# Board_0.net
KiCad netlist of a schematic drawn in EAGLE
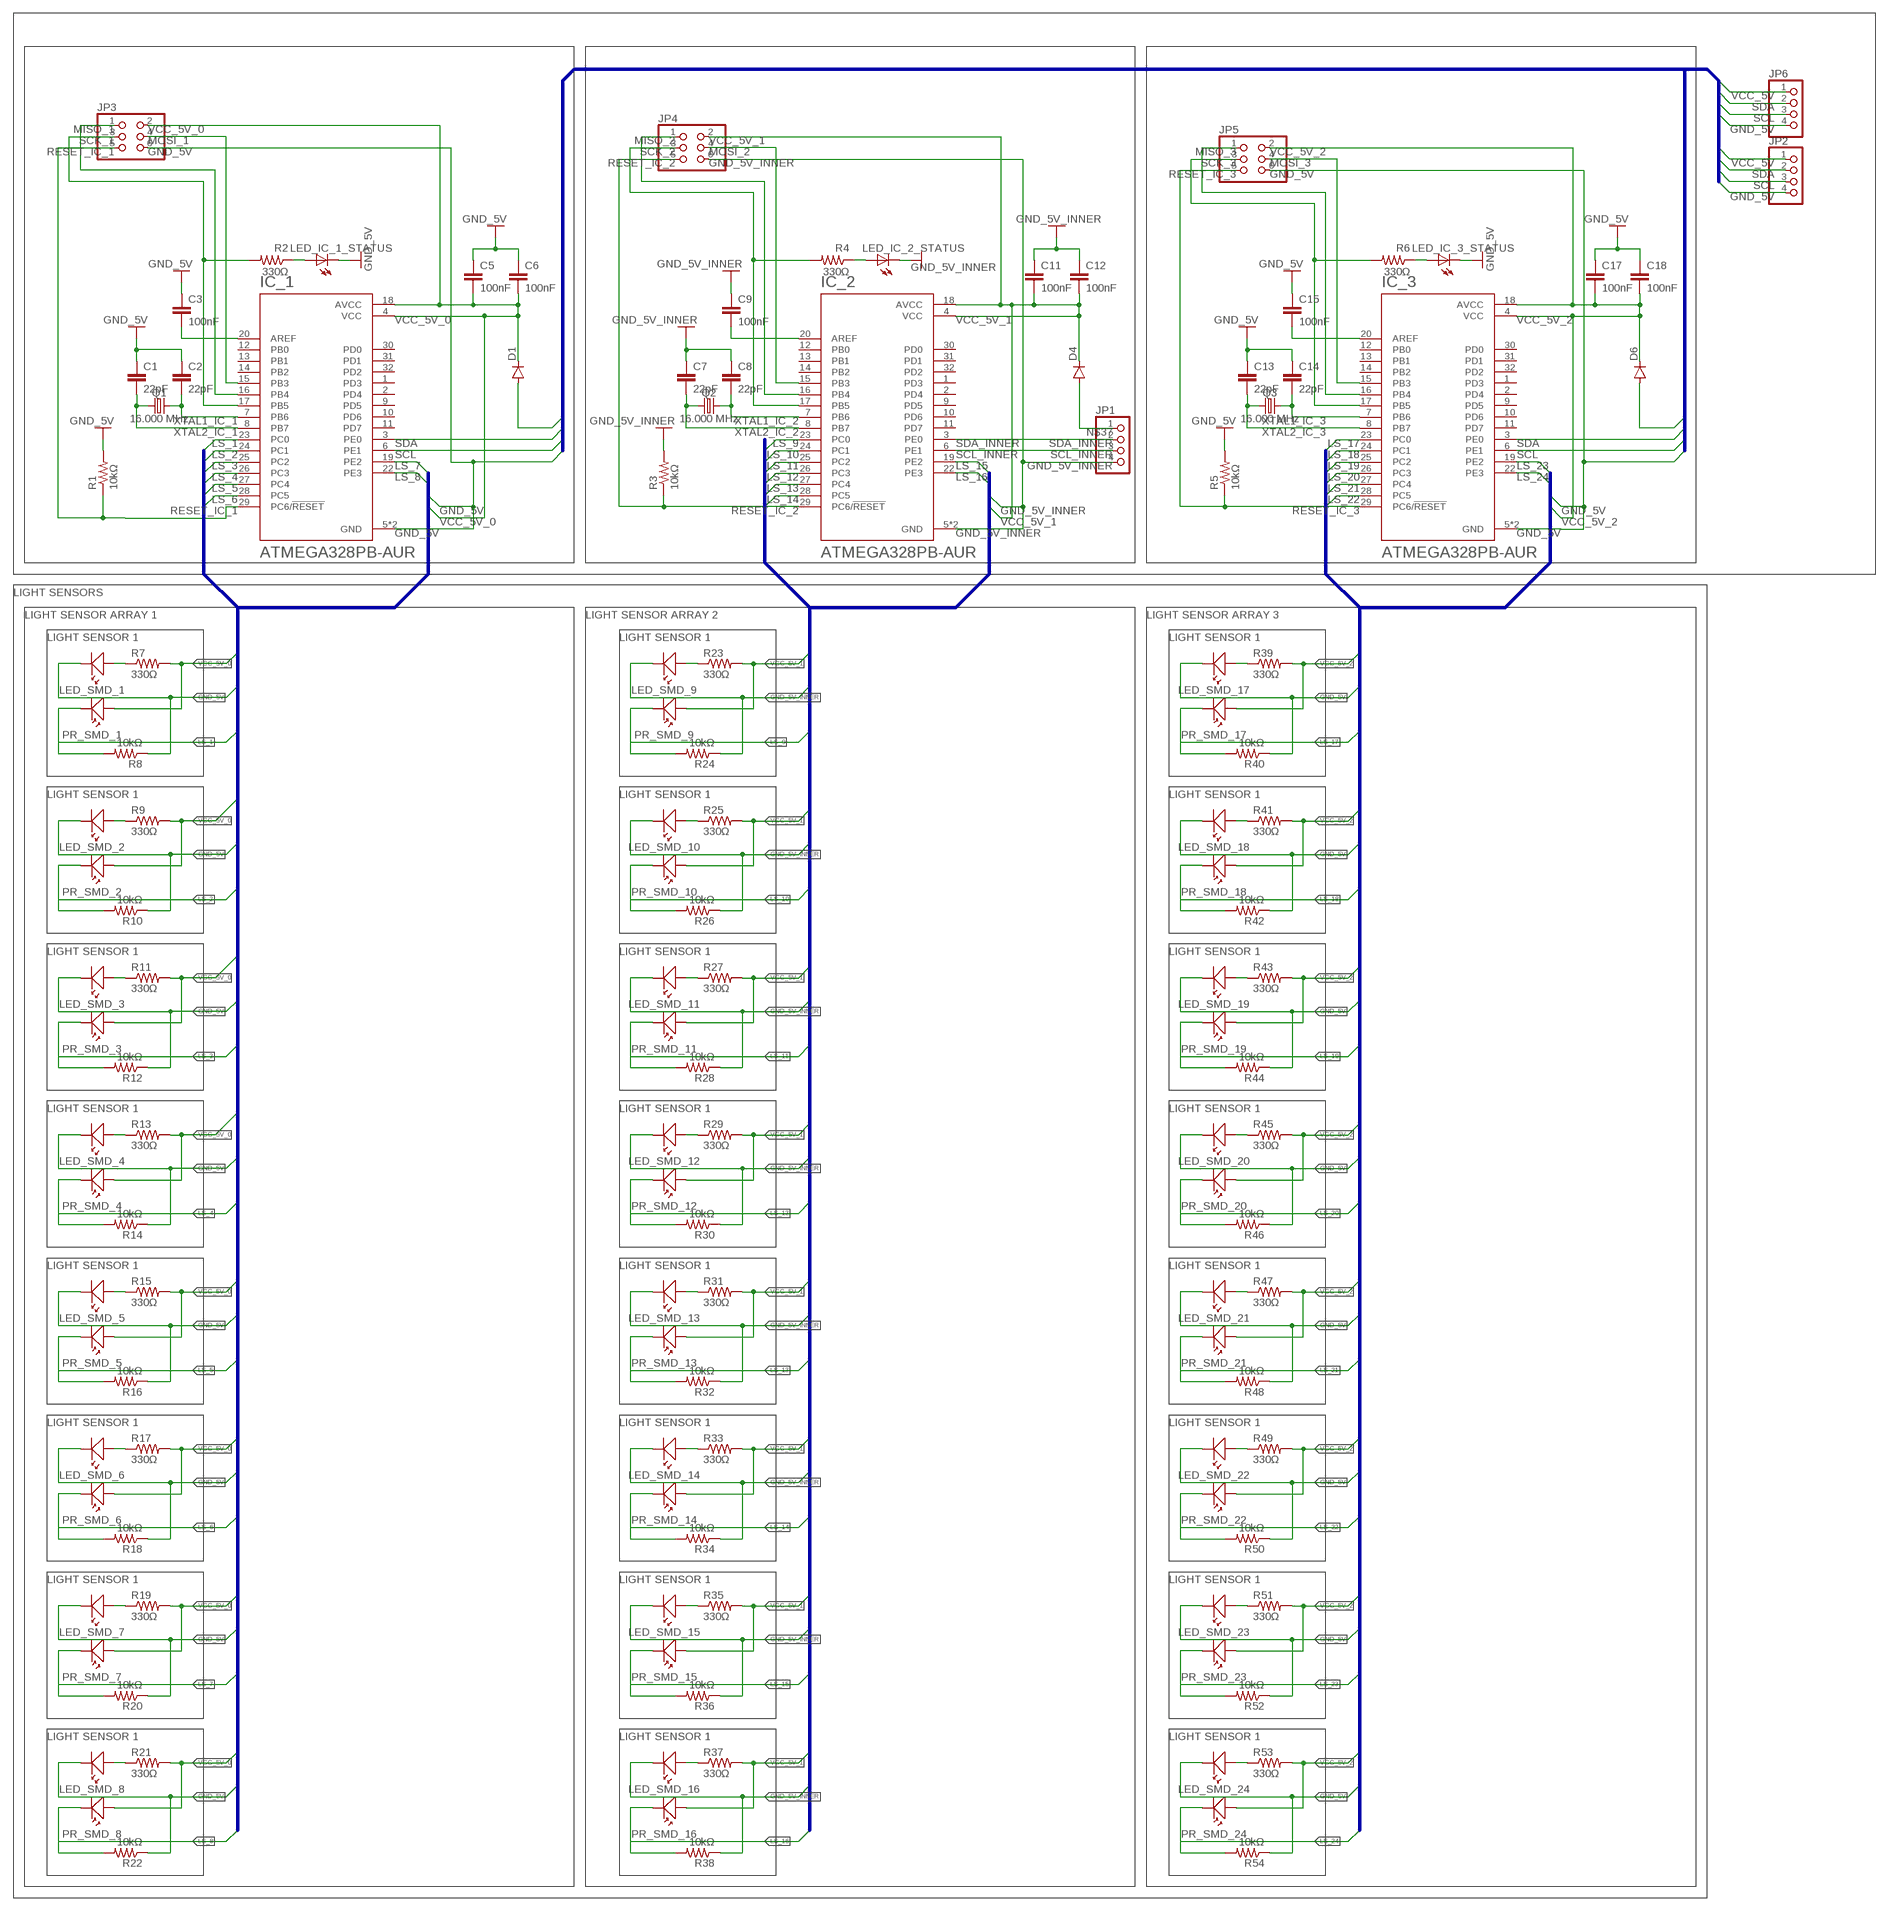
[diagram p0: schematic, sheet 1]

(export (version "E")
  (design (tool "Eeschema 10.0.6"))
  (components
    (comp (ref "C1")
      (value "22pF")
      (footprint "eagle-import:C1206")
      (libsource (lib "eagle-import") (part "C-EUC1206"))
    )
    (comp (ref "C2")
      (value "22pF")
      (footprint "eagle-import:C1206")
      (libsource (lib "eagle-import") (part "C-EUC1206"))
    )
    (comp (ref "C3")
      (value "100nF")
      (footprint "eagle-import:C1206")
      (libsource (lib "eagle-import") (part "C-EUC1206"))
    )
    (comp (ref "C5")
      (value "100nF")
      (footprint "eagle-import:C1206")
      (libsource (lib "eagle-import") (part "C-EUC1206"))
    )
    (comp (ref "C6")
      (value "100nF")
      (footprint "eagle-import:C1206")
      (libsource (lib "eagle-import") (part "C-EUC1206"))
    )
    (comp (ref "C7")
      (value "22pF")
      (footprint "eagle-import:C1206")
      (libsource (lib "eagle-import") (part "C-EUC1206"))
    )
    (comp (ref "C8")
      (value "22pF")
      (footprint "eagle-import:C1206")
      (libsource (lib "eagle-import") (part "C-EUC1206"))
    )
    (comp (ref "C9")
      (value "100nF")
      (footprint "eagle-import:C1206")
      (libsource (lib "eagle-import") (part "C-EUC1206"))
    )
    (comp (ref "C11")
      (value "100nF")
      (footprint "eagle-import:C1206")
      (libsource (lib "eagle-import") (part "C-EUC1206"))
    )
    (comp (ref "C12")
      (value "100nF")
      (footprint "eagle-import:C1206")
      (libsource (lib "eagle-import") (part "C-EUC1206"))
    )
    (comp (ref "C13")
      (value "22pF")
      (footprint "eagle-import:C1206")
      (libsource (lib "eagle-import") (part "C-EUC1206"))
    )
    (comp (ref "C14")
      (value "22pF")
      (footprint "eagle-import:C1206")
      (libsource (lib "eagle-import") (part "C-EUC1206"))
    )
    (comp (ref "C15")
      (value "100nF")
      (footprint "eagle-import:C1206")
      (libsource (lib "eagle-import") (part "C-EUC1206"))
    )
    (comp (ref "C17")
      (value "100nF")
      (footprint "eagle-import:C1206")
      (libsource (lib "eagle-import") (part "C-EUC1206"))
    )
    (comp (ref "C18")
      (value "100nF")
      (footprint "eagle-import:C1206")
      (libsource (lib "eagle-import") (part "C-EUC1206"))
    )
    (comp (ref "D1")
      (value "DIODE-SOD123")
      (footprint "eagle-import:SOD123")
      (libsource (lib "eagle-import") (part "DIODE-SOD123"))
    )
    (comp (ref "D4")
      (value "DIODE-SOD123")
      (footprint "eagle-import:SOD123")
      (libsource (lib "eagle-import") (part "DIODE-SOD123"))
    )
    (comp (ref "D6")
      (value "DIODE-SOD123")
      (footprint "eagle-import:SOD123")
      (libsource (lib "eagle-import") (part "DIODE-SOD123"))
    )
    (comp (ref "IC_1")
      (value "ATMEGA328PB-AUR")
      (footprint "eagle-import:QFP80P900X900X120-32N")
      (fields (field (name "MF") "Microchip"))
      (libsource (lib "eagle-import") (part "ATMEGA328PB-AUR"))
    )
    (comp (ref "IC_2")
      (value "ATMEGA328PB-AUR")
      (footprint "eagle-import:QFP80P900X900X120-32N")
      (fields (field (name "MF") "Microchip"))
      (libsource (lib "eagle-import") (part "ATMEGA328PB-AUR"))
    )
    (comp (ref "IC_3")
      (value "ATMEGA328PB-AUR")
      (footprint "eagle-import:QFP80P900X900X120-32N")
      (fields (field (name "MF") "Microchip"))
      (libsource (lib "eagle-import") (part "ATMEGA328PB-AUR"))
    )
    (comp (ref "JP1")
      (value "PINHD-1X4_2.54-SMD")
      (footprint "eagle-import:1X04SMD")
      (libsource (lib "eagle-import") (part "PINHD-1X4_2.54-SMD"))
    )
    (comp (ref "JP2")
      (value "PINHD-1X4_2.54-SMD")
      (footprint "eagle-import:1X04SMD")
      (libsource (lib "eagle-import") (part "PINHD-1X4_2.54-SMD"))
    )
    (comp (ref "JP3")
      (value "PINHD-2X3_2.54-SMD")
      (footprint "eagle-import:2X03SMD")
      (libsource (lib "eagle-import") (part "PINHD-2X3_2.54-SMD"))
    )
    (comp (ref "JP4")
      (value "PINHD-2X3_2.54-SMD")
      (footprint "eagle-import:2X03SMD")
      (libsource (lib "eagle-import") (part "PINHD-2X3_2.54-SMD"))
    )
    (comp (ref "JP5")
      (value "PINHD-2X3_2.54-SMD")
      (footprint "eagle-import:2X03SMD")
      (libsource (lib "eagle-import") (part "PINHD-2X3_2.54-SMD"))
    )
    (comp (ref "JP6")
      (value "PINHD-1X4_2.54-SMD")
      (footprint "eagle-import:1X04SMD")
      (libsource (lib "eagle-import") (part "PINHD-1X4_2.54-SMD"))
    )
    (comp (ref "LED_IC_1_STATUS")
      (value "LEDP-LCC-2")
      (footprint "eagle-import:P-LCC-2")
      (libsource (lib "eagle-import") (part "LEDP-LCC-2"))
    )
    (comp (ref "LED_IC_2_STATUS")
      (value "LEDP-LCC-2")
      (footprint "eagle-import:P-LCC-2")
      (libsource (lib "eagle-import") (part "LEDP-LCC-2"))
    )
    (comp (ref "LED_IC_3_STATUS")
      (value "LEDP-LCC-2")
      (footprint "eagle-import:P-LCC-2")
      (libsource (lib "eagle-import") (part "LEDP-LCC-2"))
    )
    (comp (ref "LED_SMD_1")
      (value "SMD_LED_3MM")
      (footprint "eagle-import:SMD_LED_3MM")
      (libsource (lib "eagle-import") (part "SMD_LED_3MM"))
    )
    (comp (ref "LED_SMD_2")
      (value "SMD_LED_3MM")
      (footprint "eagle-import:SMD_LED_3MM")
      (libsource (lib "eagle-import") (part "SMD_LED_3MM"))
    )
    (comp (ref "LED_SMD_3")
      (value "SMD_LED_3MM")
      (footprint "eagle-import:SMD_LED_3MM")
      (libsource (lib "eagle-import") (part "SMD_LED_3MM"))
    )
    (comp (ref "LED_SMD_4")
      (value "SMD_LED_3MM")
      (footprint "eagle-import:SMD_LED_3MM")
      (libsource (lib "eagle-import") (part "SMD_LED_3MM"))
    )
    (comp (ref "LED_SMD_5")
      (value "SMD_LED_3MM")
      (footprint "eagle-import:SMD_LED_3MM")
      (libsource (lib "eagle-import") (part "SMD_LED_3MM"))
    )
    (comp (ref "LED_SMD_6")
      (value "SMD_LED_3MM")
      (footprint "eagle-import:SMD_LED_3MM")
      (libsource (lib "eagle-import") (part "SMD_LED_3MM"))
    )
    (comp (ref "LED_SMD_7")
      (value "SMD_LED_3MM")
      (footprint "eagle-import:SMD_LED_3MM")
      (libsource (lib "eagle-import") (part "SMD_LED_3MM"))
    )
    (comp (ref "LED_SMD_8")
      (value "SMD_LED_3MM")
      (footprint "eagle-import:SMD_LED_3MM")
      (libsource (lib "eagle-import") (part "SMD_LED_3MM"))
    )
    (comp (ref "LED_SMD_9")
      (value "SMD_LED_3MM")
      (footprint "eagle-import:SMD_LED_3MM")
      (libsource (lib "eagle-import") (part "SMD_LED_3MM"))
    )
    (comp (ref "LED_SMD_10")
      (value "SMD_LED_3MM")
      (footprint "eagle-import:SMD_LED_3MM")
      (libsource (lib "eagle-import") (part "SMD_LED_3MM"))
    )
    (comp (ref "LED_SMD_11")
      (value "SMD_LED_3MM")
      (footprint "eagle-import:SMD_LED_3MM")
      (libsource (lib "eagle-import") (part "SMD_LED_3MM"))
    )
    (comp (ref "LED_SMD_12")
      (value "SMD_LED_3MM")
      (footprint "eagle-import:SMD_LED_3MM")
      (libsource (lib "eagle-import") (part "SMD_LED_3MM"))
    )
    (comp (ref "LED_SMD_13")
      (value "SMD_LED_3MM")
      (footprint "eagle-import:SMD_LED_3MM")
      (libsource (lib "eagle-import") (part "SMD_LED_3MM"))
    )
    (comp (ref "LED_SMD_14")
      (value "SMD_LED_3MM")
      (footprint "eagle-import:SMD_LED_3MM")
      (libsource (lib "eagle-import") (part "SMD_LED_3MM"))
    )
    (comp (ref "LED_SMD_15")
      (value "SMD_LED_3MM")
      (footprint "eagle-import:SMD_LED_3MM")
      (libsource (lib "eagle-import") (part "SMD_LED_3MM"))
    )
    (comp (ref "LED_SMD_16")
      (value "SMD_LED_3MM")
      (footprint "eagle-import:SMD_LED_3MM")
      (libsource (lib "eagle-import") (part "SMD_LED_3MM"))
    )
    (comp (ref "LED_SMD_17")
      (value "SMD_LED_3MM")
      (footprint "eagle-import:SMD_LED_3MM")
      (libsource (lib "eagle-import") (part "SMD_LED_3MM"))
    )
    (comp (ref "LED_SMD_18")
      (value "SMD_LED_3MM")
      (footprint "eagle-import:SMD_LED_3MM")
      (libsource (lib "eagle-import") (part "SMD_LED_3MM"))
    )
    (comp (ref "LED_SMD_19")
      (value "SMD_LED_3MM")
      (footprint "eagle-import:SMD_LED_3MM")
      (libsource (lib "eagle-import") (part "SMD_LED_3MM"))
    )
    (comp (ref "LED_SMD_20")
      (value "SMD_LED_3MM")
      (footprint "eagle-import:SMD_LED_3MM")
      (libsource (lib "eagle-import") (part "SMD_LED_3MM"))
    )
    (comp (ref "LED_SMD_21")
      (value "SMD_LED_3MM")
      (footprint "eagle-import:SMD_LED_3MM")
      (libsource (lib "eagle-import") (part "SMD_LED_3MM"))
    )
    (comp (ref "LED_SMD_22")
      (value "SMD_LED_3MM")
      (footprint "eagle-import:SMD_LED_3MM")
      (libsource (lib "eagle-import") (part "SMD_LED_3MM"))
    )
    (comp (ref "LED_SMD_23")
      (value "SMD_LED_3MM")
      (footprint "eagle-import:SMD_LED_3MM")
      (libsource (lib "eagle-import") (part "SMD_LED_3MM"))
    )
    (comp (ref "LED_SMD_24")
      (value "SMD_LED_3MM")
      (footprint "eagle-import:SMD_LED_3MM")
      (libsource (lib "eagle-import") (part "SMD_LED_3MM"))
    )
    (comp (ref "PR_SMD_1")
      (value "SMD_PHOTORESISTOR_5MM")
      (footprint "eagle-import:SMD_PHOTORESISTOR_5MM")
      (libsource (lib "eagle-import") (part "SMD_PHOTORESISTOR_5MM"))
    )
    (comp (ref "PR_SMD_2")
      (value "SMD_PHOTORESISTOR_5MM")
      (footprint "eagle-import:SMD_PHOTORESISTOR_5MM")
      (libsource (lib "eagle-import") (part "SMD_PHOTORESISTOR_5MM"))
    )
    (comp (ref "PR_SMD_3")
      (value "SMD_PHOTORESISTOR_5MM")
      (footprint "eagle-import:SMD_PHOTORESISTOR_5MM")
      (libsource (lib "eagle-import") (part "SMD_PHOTORESISTOR_5MM"))
    )
    (comp (ref "PR_SMD_4")
      (value "SMD_PHOTORESISTOR_5MM")
      (footprint "eagle-import:SMD_PHOTORESISTOR_5MM")
      (libsource (lib "eagle-import") (part "SMD_PHOTORESISTOR_5MM"))
    )
    (comp (ref "PR_SMD_5")
      (value "SMD_PHOTORESISTOR_5MM")
      (footprint "eagle-import:SMD_PHOTORESISTOR_5MM")
      (libsource (lib "eagle-import") (part "SMD_PHOTORESISTOR_5MM"))
    )
    (comp (ref "PR_SMD_6")
      (value "SMD_PHOTORESISTOR_5MM")
      (footprint "eagle-import:SMD_PHOTORESISTOR_5MM")
      (libsource (lib "eagle-import") (part "SMD_PHOTORESISTOR_5MM"))
    )
    (comp (ref "PR_SMD_7")
      (value "SMD_PHOTORESISTOR_5MM")
      (footprint "eagle-import:SMD_PHOTORESISTOR_5MM")
      (libsource (lib "eagle-import") (part "SMD_PHOTORESISTOR_5MM"))
    )
    (comp (ref "PR_SMD_8")
      (value "SMD_PHOTORESISTOR_5MM")
      (footprint "eagle-import:SMD_PHOTORESISTOR_5MM")
      (libsource (lib "eagle-import") (part "SMD_PHOTORESISTOR_5MM"))
    )
    (comp (ref "PR_SMD_9")
      (value "SMD_PHOTORESISTOR_5MM")
      (footprint "eagle-import:SMD_PHOTORESISTOR_5MM")
      (libsource (lib "eagle-import") (part "SMD_PHOTORESISTOR_5MM"))
    )
    (comp (ref "PR_SMD_10")
      (value "SMD_PHOTORESISTOR_5MM")
      (footprint "eagle-import:SMD_PHOTORESISTOR_5MM")
      (libsource (lib "eagle-import") (part "SMD_PHOTORESISTOR_5MM"))
    )
    (comp (ref "PR_SMD_11")
      (value "SMD_PHOTORESISTOR_5MM")
      (footprint "eagle-import:SMD_PHOTORESISTOR_5MM")
      (libsource (lib "eagle-import") (part "SMD_PHOTORESISTOR_5MM"))
    )
    (comp (ref "PR_SMD_12")
      (value "SMD_PHOTORESISTOR_5MM")
      (footprint "eagle-import:SMD_PHOTORESISTOR_5MM")
      (libsource (lib "eagle-import") (part "SMD_PHOTORESISTOR_5MM"))
    )
    (comp (ref "PR_SMD_13")
      (value "SMD_PHOTORESISTOR_5MM")
      (footprint "eagle-import:SMD_PHOTORESISTOR_5MM")
      (libsource (lib "eagle-import") (part "SMD_PHOTORESISTOR_5MM"))
    )
    (comp (ref "PR_SMD_14")
      (value "SMD_PHOTORESISTOR_5MM")
      (footprint "eagle-import:SMD_PHOTORESISTOR_5MM")
      (libsource (lib "eagle-import") (part "SMD_PHOTORESISTOR_5MM"))
    )
    (comp (ref "PR_SMD_15")
      (value "SMD_PHOTORESISTOR_5MM")
      (footprint "eagle-import:SMD_PHOTORESISTOR_5MM")
      (libsource (lib "eagle-import") (part "SMD_PHOTORESISTOR_5MM"))
    )
    (comp (ref "PR_SMD_16")
      (value "SMD_PHOTORESISTOR_5MM")
      (footprint "eagle-import:SMD_PHOTORESISTOR_5MM")
      (libsource (lib "eagle-import") (part "SMD_PHOTORESISTOR_5MM"))
    )
    (comp (ref "PR_SMD_17")
      (value "SMD_PHOTORESISTOR_5MM")
      (footprint "eagle-import:SMD_PHOTORESISTOR_5MM")
      (libsource (lib "eagle-import") (part "SMD_PHOTORESISTOR_5MM"))
    )
    (comp (ref "PR_SMD_18")
      (value "SMD_PHOTORESISTOR_5MM")
      (footprint "eagle-import:SMD_PHOTORESISTOR_5MM")
      (libsource (lib "eagle-import") (part "SMD_PHOTORESISTOR_5MM"))
    )
    (comp (ref "PR_SMD_19")
      (value "SMD_PHOTORESISTOR_5MM")
      (footprint "eagle-import:SMD_PHOTORESISTOR_5MM")
      (libsource (lib "eagle-import") (part "SMD_PHOTORESISTOR_5MM"))
    )
    (comp (ref "PR_SMD_20")
      (value "SMD_PHOTORESISTOR_5MM")
      (footprint "eagle-import:SMD_PHOTORESISTOR_5MM")
      (libsource (lib "eagle-import") (part "SMD_PHOTORESISTOR_5MM"))
    )
    (comp (ref "PR_SMD_21")
      (value "SMD_PHOTORESISTOR_5MM")
      (footprint "eagle-import:SMD_PHOTORESISTOR_5MM")
      (libsource (lib "eagle-import") (part "SMD_PHOTORESISTOR_5MM"))
    )
    (comp (ref "PR_SMD_22")
      (value "SMD_PHOTORESISTOR_5MM")
      (footprint "eagle-import:SMD_PHOTORESISTOR_5MM")
      (libsource (lib "eagle-import") (part "SMD_PHOTORESISTOR_5MM"))
    )
    (comp (ref "PR_SMD_23")
      (value "SMD_PHOTORESISTOR_5MM")
      (footprint "eagle-import:SMD_PHOTORESISTOR_5MM")
      (libsource (lib "eagle-import") (part "SMD_PHOTORESISTOR_5MM"))
    )
    (comp (ref "PR_SMD_24")
      (value "SMD_PHOTORESISTOR_5MM")
      (footprint "eagle-import:SMD_PHOTORESISTOR_5MM")
      (libsource (lib "eagle-import") (part "SMD_PHOTORESISTOR_5MM"))
    )
    (comp (ref "Q1")
      (value "16.000 MHz")
      (footprint "eagle-import:CRYSTAL-SMD-5X3.2-4PAD")
      (libsource (lib "eagle-import") (part "CRYSTAL-16MHZSMD-5X3.2"))
    )
    (comp (ref "Q2")
      (value "16.000 MHz")
      (footprint "eagle-import:CRYSTAL-SMD-5X3.2-4PAD")
      (libsource (lib "eagle-import") (part "CRYSTAL-16MHZSMD-5X3.2"))
    )
    (comp (ref "Q3")
      (value "16.000 MHz")
      (footprint "eagle-import:CRYSTAL-SMD-5X3.2-4PAD")
      (libsource (lib "eagle-import") (part "CRYSTAL-16MHZSMD-5X3.2"))
    )
    (comp (ref "R1")
      (value "10kΩ")
      (footprint "eagle-import:R1206")
      (libsource (lib "eagle-import") (part "R-US_R1206"))
    )
    (comp (ref "R2")
      (value "330Ω")
      (footprint "eagle-import:R1206")
      (libsource (lib "eagle-import") (part "R-US_R1206"))
    )
    (comp (ref "R3")
      (value "10kΩ")
      (footprint "eagle-import:R1206")
      (libsource (lib "eagle-import") (part "R-US_R1206"))
    )
    (comp (ref "R4")
      (value "330Ω")
      (footprint "eagle-import:R1206")
      (libsource (lib "eagle-import") (part "R-US_R1206"))
    )
    (comp (ref "R5")
      (value "10kΩ")
      (footprint "eagle-import:R1206")
      (libsource (lib "eagle-import") (part "R-US_R1206"))
    )
    (comp (ref "R6")
      (value "330Ω")
      (footprint "eagle-import:R1206")
      (libsource (lib "eagle-import") (part "R-US_R1206"))
    )
    (comp (ref "R7")
      (value "330Ω")
      (footprint "eagle-import:R1206")
      (libsource (lib "eagle-import") (part "R-US_R1206"))
    )
    (comp (ref "R8")
      (value "10kΩ")
      (footprint "eagle-import:R1206")
      (libsource (lib "eagle-import") (part "R-US_R1206"))
    )
    (comp (ref "R9")
      (value "330Ω")
      (footprint "eagle-import:R1206")
      (libsource (lib "eagle-import") (part "R-US_R1206"))
    )
    (comp (ref "R10")
      (value "10kΩ")
      (footprint "eagle-import:R1206")
      (libsource (lib "eagle-import") (part "R-US_R1206"))
    )
    (comp (ref "R11")
      (value "330Ω")
      (footprint "eagle-import:R1206")
      (libsource (lib "eagle-import") (part "R-US_R1206"))
    )
    (comp (ref "R12")
      (value "10kΩ")
      (footprint "eagle-import:R1206")
      (libsource (lib "eagle-import") (part "R-US_R1206"))
    )
    (comp (ref "R13")
      (value "330Ω")
      (footprint "eagle-import:R1206")
      (libsource (lib "eagle-import") (part "R-US_R1206"))
    )
    (comp (ref "R14")
      (value "10kΩ")
      (footprint "eagle-import:R1206")
      (libsource (lib "eagle-import") (part "R-US_R1206"))
    )
    (comp (ref "R15")
      (value "330Ω")
      (footprint "eagle-import:R1206")
      (libsource (lib "eagle-import") (part "R-US_R1206"))
    )
    (comp (ref "R16")
      (value "10kΩ")
      (footprint "eagle-import:R1206")
      (libsource (lib "eagle-import") (part "R-US_R1206"))
    )
    (comp (ref "R17")
      (value "330Ω")
      (footprint "eagle-import:R1206")
      (libsource (lib "eagle-import") (part "R-US_R1206"))
    )
    (comp (ref "R18")
      (value "10kΩ")
      (footprint "eagle-import:R1206")
      (libsource (lib "eagle-import") (part "R-US_R1206"))
    )
    (comp (ref "R19")
      (value "330Ω")
      (footprint "eagle-import:R1206")
      (libsource (lib "eagle-import") (part "R-US_R1206"))
    )
    (comp (ref "R20")
      (value "10kΩ")
      (footprint "eagle-import:R1206")
      (libsource (lib "eagle-import") (part "R-US_R1206"))
    )
    (comp (ref "R21")
      (value "330Ω")
      (footprint "eagle-import:R1206")
      (libsource (lib "eagle-import") (part "R-US_R1206"))
    )
    (comp (ref "R22")
      (value "10kΩ")
      (footprint "eagle-import:R1206")
      (libsource (lib "eagle-import") (part "R-US_R1206"))
    )
    (comp (ref "R23")
      (value "330Ω")
      (footprint "eagle-import:R1206")
      (libsource (lib "eagle-import") (part "R-US_R1206"))
    )
    (comp (ref "R24")
      (value "10kΩ")
      (footprint "eagle-import:R1206")
      (libsource (lib "eagle-import") (part "R-US_R1206"))
    )
    (comp (ref "R25")
      (value "330Ω")
      (footprint "eagle-import:R1206")
      (libsource (lib "eagle-import") (part "R-US_R1206"))
    )
    (comp (ref "R26")
      (value "10kΩ")
      (footprint "eagle-import:R1206")
      (libsource (lib "eagle-import") (part "R-US_R1206"))
    )
    (comp (ref "R27")
      (value "330Ω")
      (footprint "eagle-import:R1206")
      (libsource (lib "eagle-import") (part "R-US_R1206"))
    )
    (comp (ref "R28")
      (value "10kΩ")
      (footprint "eagle-import:R1206")
      (libsource (lib "eagle-import") (part "R-US_R1206"))
    )
    (comp (ref "R29")
      (value "330Ω")
      (footprint "eagle-import:R1206")
      (libsource (lib "eagle-import") (part "R-US_R1206"))
    )
    (comp (ref "R30")
      (value "10kΩ")
      (footprint "eagle-import:R1206")
      (libsource (lib "eagle-import") (part "R-US_R1206"))
    )
    (comp (ref "R31")
      (value "330Ω")
      (footprint "eagle-import:R1206")
      (libsource (lib "eagle-import") (part "R-US_R1206"))
    )
    (comp (ref "R32")
      (value "10kΩ")
      (footprint "eagle-import:R1206")
      (libsource (lib "eagle-import") (part "R-US_R1206"))
    )
    (comp (ref "R33")
      (value "330Ω")
      (footprint "eagle-import:R1206")
      (libsource (lib "eagle-import") (part "R-US_R1206"))
    )
    (comp (ref "R34")
      (value "10kΩ")
      (footprint "eagle-import:R1206")
      (libsource (lib "eagle-import") (part "R-US_R1206"))
    )
    (comp (ref "R35")
      (value "330Ω")
      (footprint "eagle-import:R1206")
      (libsource (lib "eagle-import") (part "R-US_R1206"))
    )
    (comp (ref "R36")
      (value "10kΩ")
      (footprint "eagle-import:R1206")
      (libsource (lib "eagle-import") (part "R-US_R1206"))
    )
    (comp (ref "R37")
      (value "330Ω")
      (footprint "eagle-import:R1206")
      (libsource (lib "eagle-import") (part "R-US_R1206"))
    )
    (comp (ref "R38")
      (value "10kΩ")
      (footprint "eagle-import:R1206")
      (libsource (lib "eagle-import") (part "R-US_R1206"))
    )
    (comp (ref "R39")
      (value "330Ω")
      (footprint "eagle-import:R1206")
      (libsource (lib "eagle-import") (part "R-US_R1206"))
    )
    (comp (ref "R40")
      (value "10kΩ")
      (footprint "eagle-import:R1206")
      (libsource (lib "eagle-import") (part "R-US_R1206"))
    )
    (comp (ref "R41")
      (value "330Ω")
      (footprint "eagle-import:R1206")
      (libsource (lib "eagle-import") (part "R-US_R1206"))
    )
    (comp (ref "R42")
      (value "10kΩ")
      (footprint "eagle-import:R1206")
      (libsource (lib "eagle-import") (part "R-US_R1206"))
    )
    (comp (ref "R43")
      (value "330Ω")
      (footprint "eagle-import:R1206")
      (libsource (lib "eagle-import") (part "R-US_R1206"))
    )
    (comp (ref "R44")
      (value "10kΩ")
      (footprint "eagle-import:R1206")
      (libsource (lib "eagle-import") (part "R-US_R1206"))
    )
    (comp (ref "R45")
      (value "330Ω")
      (footprint "eagle-import:R1206")
      (libsource (lib "eagle-import") (part "R-US_R1206"))
    )
    (comp (ref "R46")
      (value "10kΩ")
      (footprint "eagle-import:R1206")
      (libsource (lib "eagle-import") (part "R-US_R1206"))
    )
    (comp (ref "R47")
      (value "330Ω")
      (footprint "eagle-import:R1206")
      (libsource (lib "eagle-import") (part "R-US_R1206"))
    )
    (comp (ref "R48")
      (value "10kΩ")
      (footprint "eagle-import:R1206")
      (libsource (lib "eagle-import") (part "R-US_R1206"))
    )
    (comp (ref "R49")
      (value "330Ω")
      (footprint "eagle-import:R1206")
      (libsource (lib "eagle-import") (part "R-US_R1206"))
    )
    (comp (ref "R50")
      (value "10kΩ")
      (footprint "eagle-import:R1206")
      (libsource (lib "eagle-import") (part "R-US_R1206"))
    )
    (comp (ref "R51")
      (value "330Ω")
      (footprint "eagle-import:R1206")
      (libsource (lib "eagle-import") (part "R-US_R1206"))
    )
    (comp (ref "R52")
      (value "10kΩ")
      (footprint "eagle-import:R1206")
      (libsource (lib "eagle-import") (part "R-US_R1206"))
    )
    (comp (ref "R53")
      (value "330Ω")
      (footprint "eagle-import:R1206")
      (libsource (lib "eagle-import") (part "R-US_R1206"))
    )
    (comp (ref "R54")
      (value "10kΩ")
      (footprint "eagle-import:R1206")
      (libsource (lib "eagle-import") (part "R-US_R1206"))
    )
  )
  (nets
    (net (code "1") (name "/MISO_1") (class "Default")
      (node (ref "IC_1") (pin "16") (pinfunction "PB4_16") (pintype "bidirectional"))
      (node (ref "JP3") (pin "1") (pinfunction "1_1") (pintype "passive"))
    )
    (net (code "2") (name "/MISO_2") (class "Default")
      (node (ref "IC_2") (pin "16") (pinfunction "PB4_16") (pintype "bidirectional"))
      (node (ref "JP4") (pin "1") (pinfunction "1_1") (pintype "passive"))
    )
    (net (code "3") (name "/MISO_3") (class "Default")
      (node (ref "IC_3") (pin "16") (pinfunction "PB4_16") (pintype "bidirectional"))
      (node (ref "JP5") (pin "1") (pinfunction "1_1") (pintype "passive"))
    )
    (net (code "4") (name "/MOSI_1") (class "Default")
      (node (ref "IC_1") (pin "15") (pinfunction "PB3_15") (pintype "bidirectional"))
      (node (ref "JP3") (pin "4") (pinfunction "4_4") (pintype "passive"))
    )
    (net (code "5") (name "/MOSI_2") (class "Default")
      (node (ref "IC_2") (pin "15") (pinfunction "PB3_15") (pintype "bidirectional"))
      (node (ref "JP4") (pin "4") (pinfunction "4_4") (pintype "passive"))
    )
    (net (code "6") (name "/MOSI_3") (class "Default")
      (node (ref "IC_3") (pin "15") (pinfunction "PB3_15") (pintype "bidirectional"))
      (node (ref "JP5") (pin "4") (pinfunction "4_4") (pintype "passive"))
    )
    (net (code "7") (name "/N$37") (class "Default")
      (node (ref "D4") (pin "A") (pinfunction "A_A") (pintype "passive"))
      (node (ref "JP1") (pin "1") (pinfunction "1_1") (pintype "passive"))
    )
    (net (code "8") (name "/RESET_IC_1") (class "Default")
      (node (ref "IC_1") (pin "29") (pinfunction "PC6/~{RESET}_29") (pintype "bidirectional"))
      (node (ref "JP3") (pin "5") (pinfunction "5_5") (pintype "passive"))
      (node (ref "R1") (pin "1") (pinfunction "1_1") (pintype "passive"))
    )
    (net (code "9") (name "/RESET_IC_2") (class "Default")
      (node (ref "IC_2") (pin "29") (pinfunction "PC6/~{RESET}_29") (pintype "bidirectional"))
      (node (ref "JP4") (pin "5") (pinfunction "5_5") (pintype "passive"))
      (node (ref "R3") (pin "1") (pinfunction "1_1") (pintype "passive"))
    )
    (net (code "10") (name "/RESET_IC_3") (class "Default")
      (node (ref "IC_3") (pin "29") (pinfunction "PC6/~{RESET}_29") (pintype "bidirectional"))
      (node (ref "JP5") (pin "5") (pinfunction "5_5") (pintype "passive"))
      (node (ref "R5") (pin "1") (pinfunction "1_1") (pintype "passive"))
    )
    (net (code "11") (name "/SCK_1") (class "Default")
      (node (ref "IC_1") (pin "17") (pinfunction "PB5_17") (pintype "bidirectional"))
      (node (ref "JP3") (pin "3") (pinfunction "3_3") (pintype "passive"))
      (node (ref "R2") (pin "2") (pinfunction "2_2") (pintype "passive"))
    )
    (net (code "12") (name "/SCK_2") (class "Default")
      (node (ref "IC_2") (pin "17") (pinfunction "PB5_17") (pintype "bidirectional"))
      (node (ref "JP4") (pin "3") (pinfunction "3_3") (pintype "passive"))
      (node (ref "R4") (pin "2") (pinfunction "2_2") (pintype "passive"))
    )
    (net (code "13") (name "/SCK_3") (class "Default")
      (node (ref "IC_3") (pin "17") (pinfunction "PB5_17") (pintype "bidirectional"))
      (node (ref "JP5") (pin "3") (pinfunction "3_3") (pintype "passive"))
      (node (ref "R6") (pin "2") (pinfunction "2_2") (pintype "passive"))
    )
    (net (code "14") (name "/SCL") (class "Default")
      (node (ref "IC_1") (pin "6") (pinfunction "PE1_6") (pintype "bidirectional"))
      (node (ref "IC_3") (pin "6") (pinfunction "PE1_6") (pintype "bidirectional"))
      (node (ref "JP2") (pin "3") (pinfunction "3_3") (pintype "passive"))
      (node (ref "JP6") (pin "3") (pinfunction "3_3") (pintype "passive"))
    )
    (net (code "15") (name "/SCL_INNER") (class "Default")
      (node (ref "IC_2") (pin "6") (pinfunction "PE1_6") (pintype "bidirectional"))
      (node (ref "JP1") (pin "3") (pinfunction "3_3") (pintype "passive"))
    )
    (net (code "16") (name "/SDA") (class "Default")
      (node (ref "IC_1") (pin "3") (pinfunction "PE0_3") (pintype "bidirectional"))
      (node (ref "IC_3") (pin "3") (pinfunction "PE0_3") (pintype "bidirectional"))
      (node (ref "JP2") (pin "2") (pinfunction "2_2") (pintype "passive"))
      (node (ref "JP6") (pin "2") (pinfunction "2_2") (pintype "passive"))
    )
    (net (code "17") (name "/SDA_INNER") (class "Default")
      (node (ref "IC_2") (pin "3") (pinfunction "PE0_3") (pintype "bidirectional"))
      (node (ref "JP1") (pin "2") (pinfunction "2_2") (pintype "passive"))
    )
    (net (code "18") (name "/VCC_5V") (class "Default")
      (node (ref "D1") (pin "A") (pinfunction "A_A") (pintype "passive"))
      (node (ref "D6") (pin "A") (pinfunction "A_A") (pintype "passive"))
      (node (ref "JP2") (pin "1") (pinfunction "1_1") (pintype "passive"))
      (node (ref "JP6") (pin "1") (pinfunction "1_1") (pintype "passive"))
    )
    (net (code "19") (name "/XTAL1_IC_1") (class "Default")
      (node (ref "C2") (pin "2") (pinfunction "2_2") (pintype "passive"))
      (node (ref "IC_1") (pin "7") (pinfunction "PB6_7") (pintype "bidirectional"))
      (node (ref "Q1") (pin "3") (pinfunction "2_3") (pintype "passive"))
    )
    (net (code "20") (name "/XTAL1_IC_2") (class "Default")
      (node (ref "C8") (pin "2") (pinfunction "2_2") (pintype "passive"))
      (node (ref "IC_2") (pin "7") (pinfunction "PB6_7") (pintype "bidirectional"))
      (node (ref "Q2") (pin "3") (pinfunction "2_3") (pintype "passive"))
    )
    (net (code "21") (name "/XTAL1_IC_3") (class "Default")
      (node (ref "C14") (pin "2") (pinfunction "2_2") (pintype "passive"))
      (node (ref "IC_3") (pin "7") (pinfunction "PB6_7") (pintype "bidirectional"))
      (node (ref "Q3") (pin "3") (pinfunction "2_3") (pintype "passive"))
    )
    (net (code "22") (name "/XTAL2_IC_1") (class "Default")
      (node (ref "C1") (pin "2") (pinfunction "2_2") (pintype "passive"))
      (node (ref "IC_1") (pin "8") (pinfunction "PB7_8") (pintype "bidirectional"))
      (node (ref "Q1") (pin "1") (pinfunction "1_1") (pintype "passive"))
    )
    (net (code "23") (name "/XTAL2_IC_2") (class "Default")
      (node (ref "C7") (pin "2") (pinfunction "2_2") (pintype "passive"))
      (node (ref "IC_2") (pin "8") (pinfunction "PB7_8") (pintype "bidirectional"))
      (node (ref "Q2") (pin "1") (pinfunction "1_1") (pintype "passive"))
    )
    (net (code "24") (name "/XTAL2_IC_3") (class "Default")
      (node (ref "C13") (pin "2") (pinfunction "2_2") (pintype "passive"))
      (node (ref "IC_3") (pin "8") (pinfunction "PB7_8") (pintype "bidirectional"))
      (node (ref "Q3") (pin "1") (pinfunction "1_1") (pintype "passive"))
    )
    (net (code "25") (name "GND_5V") (class "Default")
      (node (ref "C1") (pin "1") (pinfunction "1_1") (pintype "passive"))
      (node (ref "C13") (pin "1") (pinfunction "1_1") (pintype "passive"))
      (node (ref "C14") (pin "1") (pinfunction "1_1") (pintype "passive"))
      (node (ref "C15") (pin "1") (pinfunction "1_1") (pintype "passive"))
      (node (ref "C17") (pin "1") (pinfunction "1_1") (pintype "passive"))
      (node (ref "C18") (pin "1") (pinfunction "1_1") (pintype "passive"))
      (node (ref "C2") (pin "1") (pinfunction "1_1") (pintype "passive"))
      (node (ref "C3") (pin "1") (pinfunction "1_1") (pintype "passive"))
      (node (ref "C5") (pin "1") (pinfunction "1_1") (pintype "passive"))
      (node (ref "C6") (pin "1") (pinfunction "1_1") (pintype "passive"))
      (node (ref "IC_1") (pin "21") (pinfunction "GND_21") (pintype "power_in"))
      (node (ref "IC_1") (pin "5") (pinfunction "GND_5") (pintype "power_in"))
      (node (ref "IC_3") (pin "21") (pinfunction "GND_21") (pintype "power_in"))
      (node (ref "IC_3") (pin "5") (pinfunction "GND_5") (pintype "power_in"))
      (node (ref "JP2") (pin "4") (pinfunction "4_4") (pintype "passive"))
      (node (ref "JP3") (pin "6") (pinfunction "6_6") (pintype "passive"))
      (node (ref "JP5") (pin "6") (pinfunction "6_6") (pintype "passive"))
      (node (ref "JP6") (pin "4") (pinfunction "4_4") (pintype "passive"))
      (node (ref "LED_IC_1_STATUS") (pin "C") (pinfunction "C_C") (pintype "passive"))
      (node (ref "LED_IC_3_STATUS") (pin "C") (pinfunction "C_C") (pintype "passive"))
      (node (ref "LED_SMD_1") (pin "GND") (pinfunction "GND_GND") (pintype "output"))
      (node (ref "LED_SMD_17") (pin "GND") (pinfunction "GND_GND") (pintype "output"))
      (node (ref "LED_SMD_18") (pin "GND") (pinfunction "GND_GND") (pintype "output"))
      (node (ref "LED_SMD_19") (pin "GND") (pinfunction "GND_GND") (pintype "output"))
      (node (ref "LED_SMD_2") (pin "GND") (pinfunction "GND_GND") (pintype "output"))
      (node (ref "LED_SMD_20") (pin "GND") (pinfunction "GND_GND") (pintype "output"))
      (node (ref "LED_SMD_21") (pin "GND") (pinfunction "GND_GND") (pintype "output"))
      (node (ref "LED_SMD_22") (pin "GND") (pinfunction "GND_GND") (pintype "output"))
      (node (ref "LED_SMD_23") (pin "GND") (pinfunction "GND_GND") (pintype "output"))
      (node (ref "LED_SMD_24") (pin "GND") (pinfunction "GND_GND") (pintype "output"))
      (node (ref "LED_SMD_3") (pin "GND") (pinfunction "GND_GND") (pintype "output"))
      (node (ref "LED_SMD_4") (pin "GND") (pinfunction "GND_GND") (pintype "output"))
      (node (ref "LED_SMD_5") (pin "GND") (pinfunction "GND_GND") (pintype "output"))
      (node (ref "LED_SMD_6") (pin "GND") (pinfunction "GND_GND") (pintype "output"))
      (node (ref "LED_SMD_7") (pin "GND") (pinfunction "GND_GND") (pintype "output"))
      (node (ref "LED_SMD_8") (pin "GND") (pinfunction "GND_GND") (pintype "output"))
      (node (ref "R1") (pin "2") (pinfunction "2_2") (pintype "passive"))
      (node (ref "R10") (pin "1") (pinfunction "1_1") (pintype "passive"))
      (node (ref "R12") (pin "1") (pinfunction "1_1") (pintype "passive"))
      (node (ref "R14") (pin "1") (pinfunction "1_1") (pintype "passive"))
      (node (ref "R16") (pin "1") (pinfunction "1_1") (pintype "passive"))
      (node (ref "R18") (pin "1") (pinfunction "1_1") (pintype "passive"))
      (node (ref "R20") (pin "1") (pinfunction "1_1") (pintype "passive"))
      (node (ref "R22") (pin "1") (pinfunction "1_1") (pintype "passive"))
      (node (ref "R40") (pin "1") (pinfunction "1_1") (pintype "passive"))
      (node (ref "R42") (pin "1") (pinfunction "1_1") (pintype "passive"))
      (node (ref "R44") (pin "1") (pinfunction "1_1") (pintype "passive"))
      (node (ref "R46") (pin "1") (pinfunction "1_1") (pintype "passive"))
      (node (ref "R48") (pin "1") (pinfunction "1_1") (pintype "passive"))
      (node (ref "R5") (pin "2") (pinfunction "2_2") (pintype "passive"))
      (node (ref "R50") (pin "1") (pinfunction "1_1") (pintype "passive"))
      (node (ref "R52") (pin "1") (pinfunction "1_1") (pintype "passive"))
      (node (ref "R54") (pin "1") (pinfunction "1_1") (pintype "passive"))
      (node (ref "R8") (pin "1") (pinfunction "1_1") (pintype "passive"))
    )
    (net (code "26") (name "GND_5V_INNER") (class "Default")
      (node (ref "C11") (pin "1") (pinfunction "1_1") (pintype "passive"))
      (node (ref "C12") (pin "1") (pinfunction "1_1") (pintype "passive"))
      (node (ref "C7") (pin "1") (pinfunction "1_1") (pintype "passive"))
      (node (ref "C8") (pin "1") (pinfunction "1_1") (pintype "passive"))
      (node (ref "C9") (pin "1") (pinfunction "1_1") (pintype "passive"))
      (node (ref "IC_2") (pin "21") (pinfunction "GND_21") (pintype "power_in"))
      (node (ref "IC_2") (pin "5") (pinfunction "GND_5") (pintype "power_in"))
      (node (ref "JP1") (pin "4") (pinfunction "4_4") (pintype "passive"))
      (node (ref "JP4") (pin "6") (pinfunction "6_6") (pintype "passive"))
      (node (ref "LED_IC_2_STATUS") (pin "C") (pinfunction "C_C") (pintype "passive"))
      (node (ref "LED_SMD_10") (pin "GND") (pinfunction "GND_GND") (pintype "output"))
      (node (ref "LED_SMD_11") (pin "GND") (pinfunction "GND_GND") (pintype "output"))
      (node (ref "LED_SMD_12") (pin "GND") (pinfunction "GND_GND") (pintype "output"))
      (node (ref "LED_SMD_13") (pin "GND") (pinfunction "GND_GND") (pintype "output"))
      (node (ref "LED_SMD_14") (pin "GND") (pinfunction "GND_GND") (pintype "output"))
      (node (ref "LED_SMD_15") (pin "GND") (pinfunction "GND_GND") (pintype "output"))
      (node (ref "LED_SMD_16") (pin "GND") (pinfunction "GND_GND") (pintype "output"))
      (node (ref "LED_SMD_9") (pin "GND") (pinfunction "GND_GND") (pintype "output"))
      (node (ref "R24") (pin "1") (pinfunction "1_1") (pintype "passive"))
      (node (ref "R26") (pin "1") (pinfunction "1_1") (pintype "passive"))
      (node (ref "R28") (pin "1") (pinfunction "1_1") (pintype "passive"))
      (node (ref "R3") (pin "2") (pinfunction "2_2") (pintype "passive"))
      (node (ref "R30") (pin "1") (pinfunction "1_1") (pintype "passive"))
      (node (ref "R32") (pin "1") (pinfunction "1_1") (pintype "passive"))
      (node (ref "R34") (pin "1") (pinfunction "1_1") (pintype "passive"))
      (node (ref "R36") (pin "1") (pinfunction "1_1") (pintype "passive"))
      (node (ref "R38") (pin "1") (pinfunction "1_1") (pintype "passive"))
    )
    (net (code "27") (name "LS_1") (class "Default")
      (node (ref "IC_1") (pin "23") (pinfunction "PC0_23") (pintype "bidirectional"))
      (node (ref "PR_SMD_1") (pin "GND") (pinfunction "GND_GND") (pintype "output"))
      (node (ref "R8") (pin "2") (pinfunction "2_2") (pintype "passive"))
    )
    (net (code "28") (name "LS_2") (class "Default")
      (node (ref "IC_1") (pin "24") (pinfunction "PC1_24") (pintype "bidirectional"))
      (node (ref "PR_SMD_2") (pin "GND") (pinfunction "GND_GND") (pintype "output"))
      (node (ref "R10") (pin "2") (pinfunction "2_2") (pintype "passive"))
    )
    (net (code "29") (name "LS_3") (class "Default")
      (node (ref "IC_1") (pin "25") (pinfunction "PC2_25") (pintype "bidirectional"))
      (node (ref "PR_SMD_3") (pin "GND") (pinfunction "GND_GND") (pintype "output"))
      (node (ref "R12") (pin "2") (pinfunction "2_2") (pintype "passive"))
    )
    (net (code "30") (name "LS_4") (class "Default")
      (node (ref "IC_1") (pin "26") (pinfunction "PC3_26") (pintype "bidirectional"))
      (node (ref "PR_SMD_4") (pin "GND") (pinfunction "GND_GND") (pintype "output"))
      (node (ref "R14") (pin "2") (pinfunction "2_2") (pintype "passive"))
    )
    (net (code "31") (name "LS_5") (class "Default")
      (node (ref "IC_1") (pin "27") (pinfunction "PC4_27") (pintype "bidirectional"))
      (node (ref "PR_SMD_5") (pin "GND") (pinfunction "GND_GND") (pintype "output"))
      (node (ref "R16") (pin "2") (pinfunction "2_2") (pintype "passive"))
    )
    (net (code "32") (name "LS_6") (class "Default")
      (node (ref "IC_1") (pin "28") (pinfunction "PC5_28") (pintype "bidirectional"))
      (node (ref "PR_SMD_6") (pin "GND") (pinfunction "GND_GND") (pintype "output"))
      (node (ref "R18") (pin "2") (pinfunction "2_2") (pintype "passive"))
    )
    (net (code "33") (name "LS_7") (class "Default")
      (node (ref "IC_1") (pin "19") (pinfunction "PE2_19") (pintype "bidirectional"))
      (node (ref "PR_SMD_7") (pin "GND") (pinfunction "GND_GND") (pintype "output"))
      (node (ref "R20") (pin "2") (pinfunction "2_2") (pintype "passive"))
    )
    (net (code "34") (name "LS_8") (class "Default")
      (node (ref "IC_1") (pin "22") (pinfunction "PE3_22") (pintype "bidirectional"))
      (node (ref "PR_SMD_8") (pin "GND") (pinfunction "GND_GND") (pintype "output"))
      (node (ref "R22") (pin "2") (pinfunction "2_2") (pintype "passive"))
    )
    (net (code "35") (name "LS_9") (class "Default")
      (node (ref "IC_2") (pin "23") (pinfunction "PC0_23") (pintype "bidirectional"))
      (node (ref "PR_SMD_9") (pin "GND") (pinfunction "GND_GND") (pintype "output"))
      (node (ref "R24") (pin "2") (pinfunction "2_2") (pintype "passive"))
    )
    (net (code "36") (name "LS_10") (class "Default")
      (node (ref "IC_2") (pin "24") (pinfunction "PC1_24") (pintype "bidirectional"))
      (node (ref "PR_SMD_10") (pin "GND") (pinfunction "GND_GND") (pintype "output"))
      (node (ref "R26") (pin "2") (pinfunction "2_2") (pintype "passive"))
    )
    (net (code "37") (name "LS_11") (class "Default")
      (node (ref "IC_2") (pin "25") (pinfunction "PC2_25") (pintype "bidirectional"))
      (node (ref "PR_SMD_11") (pin "GND") (pinfunction "GND_GND") (pintype "output"))
      (node (ref "R28") (pin "2") (pinfunction "2_2") (pintype "passive"))
    )
    (net (code "38") (name "LS_12") (class "Default")
      (node (ref "IC_2") (pin "26") (pinfunction "PC3_26") (pintype "bidirectional"))
      (node (ref "PR_SMD_12") (pin "GND") (pinfunction "GND_GND") (pintype "output"))
      (node (ref "R30") (pin "2") (pinfunction "2_2") (pintype "passive"))
    )
    (net (code "39") (name "LS_13") (class "Default")
      (node (ref "IC_2") (pin "27") (pinfunction "PC4_27") (pintype "bidirectional"))
      (node (ref "PR_SMD_13") (pin "GND") (pinfunction "GND_GND") (pintype "output"))
      (node (ref "R32") (pin "2") (pinfunction "2_2") (pintype "passive"))
    )
    (net (code "40") (name "LS_14") (class "Default")
      (node (ref "IC_2") (pin "28") (pinfunction "PC5_28") (pintype "bidirectional"))
      (node (ref "PR_SMD_14") (pin "GND") (pinfunction "GND_GND") (pintype "output"))
      (node (ref "R34") (pin "2") (pinfunction "2_2") (pintype "passive"))
    )
    (net (code "41") (name "LS_15") (class "Default")
      (node (ref "IC_2") (pin "19") (pinfunction "PE2_19") (pintype "bidirectional"))
      (node (ref "PR_SMD_15") (pin "GND") (pinfunction "GND_GND") (pintype "output"))
      (node (ref "R36") (pin "2") (pinfunction "2_2") (pintype "passive"))
    )
    (net (code "42") (name "LS_16") (class "Default")
      (node (ref "IC_2") (pin "22") (pinfunction "PE3_22") (pintype "bidirectional"))
      (node (ref "PR_SMD_16") (pin "GND") (pinfunction "GND_GND") (pintype "output"))
      (node (ref "R38") (pin "2") (pinfunction "2_2") (pintype "passive"))
    )
    (net (code "43") (name "LS_17") (class "Default")
      (node (ref "IC_3") (pin "23") (pinfunction "PC0_23") (pintype "bidirectional"))
      (node (ref "PR_SMD_17") (pin "GND") (pinfunction "GND_GND") (pintype "output"))
      (node (ref "R40") (pin "2") (pinfunction "2_2") (pintype "passive"))
    )
    (net (code "44") (name "LS_18") (class "Default")
      (node (ref "IC_3") (pin "24") (pinfunction "PC1_24") (pintype "bidirectional"))
      (node (ref "PR_SMD_18") (pin "GND") (pinfunction "GND_GND") (pintype "output"))
      (node (ref "R42") (pin "2") (pinfunction "2_2") (pintype "passive"))
    )
    (net (code "45") (name "LS_19") (class "Default")
      (node (ref "IC_3") (pin "25") (pinfunction "PC2_25") (pintype "bidirectional"))
      (node (ref "PR_SMD_19") (pin "GND") (pinfunction "GND_GND") (pintype "output"))
      (node (ref "R44") (pin "2") (pinfunction "2_2") (pintype "passive"))
    )
    (net (code "46") (name "LS_20") (class "Default")
      (node (ref "IC_3") (pin "26") (pinfunction "PC3_26") (pintype "bidirectional"))
      (node (ref "PR_SMD_20") (pin "GND") (pinfunction "GND_GND") (pintype "output"))
      (node (ref "R46") (pin "2") (pinfunction "2_2") (pintype "passive"))
    )
    (net (code "47") (name "LS_21") (class "Default")
      (node (ref "IC_3") (pin "27") (pinfunction "PC4_27") (pintype "bidirectional"))
      (node (ref "PR_SMD_21") (pin "GND") (pinfunction "GND_GND") (pintype "output"))
      (node (ref "R48") (pin "2") (pinfunction "2_2") (pintype "passive"))
    )
    (net (code "48") (name "LS_22") (class "Default")
      (node (ref "IC_3") (pin "28") (pinfunction "PC5_28") (pintype "bidirectional"))
      (node (ref "PR_SMD_22") (pin "GND") (pinfunction "GND_GND") (pintype "output"))
      (node (ref "R50") (pin "2") (pinfunction "2_2") (pintype "passive"))
    )
    (net (code "49") (name "LS_23") (class "Default")
      (node (ref "IC_3") (pin "19") (pinfunction "PE2_19") (pintype "bidirectional"))
      (node (ref "PR_SMD_23") (pin "GND") (pinfunction "GND_GND") (pintype "output"))
      (node (ref "R52") (pin "2") (pinfunction "2_2") (pintype "passive"))
    )
    (net (code "50") (name "LS_24") (class "Default")
      (node (ref "IC_3") (pin "22") (pinfunction "PE3_22") (pintype "bidirectional"))
      (node (ref "PR_SMD_24") (pin "GND") (pinfunction "GND_GND") (pintype "output"))
      (node (ref "R54") (pin "2") (pinfunction "2_2") (pintype "passive"))
    )
    (net (code "51") (name "Net-(IC_1-AREF)") (class "Default")
      (node (ref "C3") (pin "2") (pinfunction "2_2") (pintype "passive"))
      (node (ref "IC_1") (pin "20") (pinfunction "AREF_20") (pintype "input"))
    )
    (net (code "52") (name "Net-(IC_2-AREF)") (class "Default")
      (node (ref "C9") (pin "2") (pinfunction "2_2") (pintype "passive"))
      (node (ref "IC_2") (pin "20") (pinfunction "AREF_20") (pintype "input"))
    )
    (net (code "53") (name "Net-(IC_3-AREF)") (class "Default")
      (node (ref "C15") (pin "2") (pinfunction "2_2") (pintype "passive"))
      (node (ref "IC_3") (pin "20") (pinfunction "AREF_20") (pintype "input"))
    )
    (net (code "54") (name "Net-(LED_IC_1_STATUS-PadA)") (class "Default")
      (node (ref "LED_IC_1_STATUS") (pin "A") (pinfunction "A_A") (pintype "passive"))
      (node (ref "R2") (pin "1") (pinfunction "1_1") (pintype "passive"))
    )
    (net (code "55") (name "Net-(LED_IC_2_STATUS-PadA)") (class "Default")
      (node (ref "LED_IC_2_STATUS") (pin "A") (pinfunction "A_A") (pintype "passive"))
      (node (ref "R4") (pin "1") (pinfunction "1_1") (pintype "passive"))
    )
    (net (code "56") (name "Net-(LED_IC_3_STATUS-PadA)") (class "Default")
      (node (ref "LED_IC_3_STATUS") (pin "A") (pinfunction "A_A") (pintype "passive"))
      (node (ref "R6") (pin "1") (pinfunction "1_1") (pintype "passive"))
    )
    (net (code "57") (name "Net-(LED_SMD_1-PadVIN)") (class "Default")
      (node (ref "LED_SMD_1") (pin "VIN") (pinfunction "VIN_VIN") (pintype "input"))
      (node (ref "R7") (pin "1") (pinfunction "1_1") (pintype "passive"))
    )
    (net (code "58") (name "Net-(LED_SMD_2-PadVIN)") (class "Default")
      (node (ref "LED_SMD_2") (pin "VIN") (pinfunction "VIN_VIN") (pintype "input"))
      (node (ref "R9") (pin "1") (pinfunction "1_1") (pintype "passive"))
    )
    (net (code "59") (name "Net-(LED_SMD_3-PadVIN)") (class "Default")
      (node (ref "LED_SMD_3") (pin "VIN") (pinfunction "VIN_VIN") (pintype "input"))
      (node (ref "R11") (pin "1") (pinfunction "1_1") (pintype "passive"))
    )
    (net (code "60") (name "Net-(LED_SMD_4-PadVIN)") (class "Default")
      (node (ref "LED_SMD_4") (pin "VIN") (pinfunction "VIN_VIN") (pintype "input"))
      (node (ref "R13") (pin "1") (pinfunction "1_1") (pintype "passive"))
    )
    (net (code "61") (name "Net-(LED_SMD_5-PadVIN)") (class "Default")
      (node (ref "LED_SMD_5") (pin "VIN") (pinfunction "VIN_VIN") (pintype "input"))
      (node (ref "R15") (pin "1") (pinfunction "1_1") (pintype "passive"))
    )
    (net (code "62") (name "Net-(LED_SMD_6-PadVIN)") (class "Default")
      (node (ref "LED_SMD_6") (pin "VIN") (pinfunction "VIN_VIN") (pintype "input"))
      (node (ref "R17") (pin "1") (pinfunction "1_1") (pintype "passive"))
    )
    (net (code "63") (name "Net-(LED_SMD_7-PadVIN)") (class "Default")
      (node (ref "LED_SMD_7") (pin "VIN") (pinfunction "VIN_VIN") (pintype "input"))
      (node (ref "R19") (pin "1") (pinfunction "1_1") (pintype "passive"))
    )
    (net (code "64") (name "Net-(LED_SMD_8-PadVIN)") (class "Default")
      (node (ref "LED_SMD_8") (pin "VIN") (pinfunction "VIN_VIN") (pintype "input"))
      (node (ref "R21") (pin "1") (pinfunction "1_1") (pintype "passive"))
    )
    (net (code "65") (name "Net-(LED_SMD_9-PadVIN)") (class "Default")
      (node (ref "LED_SMD_9") (pin "VIN") (pinfunction "VIN_VIN") (pintype "input"))
      (node (ref "R23") (pin "1") (pinfunction "1_1") (pintype "passive"))
    )
    (net (code "66") (name "Net-(LED_SMD_10-PadVIN)") (class "Default")
      (node (ref "LED_SMD_10") (pin "VIN") (pinfunction "VIN_VIN") (pintype "input"))
      (node (ref "R25") (pin "1") (pinfunction "1_1") (pintype "passive"))
    )
    (net (code "67") (name "Net-(LED_SMD_11-PadVIN)") (class "Default")
      (node (ref "LED_SMD_11") (pin "VIN") (pinfunction "VIN_VIN") (pintype "input"))
      (node (ref "R27") (pin "1") (pinfunction "1_1") (pintype "passive"))
    )
    (net (code "68") (name "Net-(LED_SMD_12-PadVIN)") (class "Default")
      (node (ref "LED_SMD_12") (pin "VIN") (pinfunction "VIN_VIN") (pintype "input"))
      (node (ref "R29") (pin "1") (pinfunction "1_1") (pintype "passive"))
    )
    (net (code "69") (name "Net-(LED_SMD_13-PadVIN)") (class "Default")
      (node (ref "LED_SMD_13") (pin "VIN") (pinfunction "VIN_VIN") (pintype "input"))
      (node (ref "R31") (pin "1") (pinfunction "1_1") (pintype "passive"))
    )
    (net (code "70") (name "Net-(LED_SMD_14-PadVIN)") (class "Default")
      (node (ref "LED_SMD_14") (pin "VIN") (pinfunction "VIN_VIN") (pintype "input"))
      (node (ref "R33") (pin "1") (pinfunction "1_1") (pintype "passive"))
    )
    (net (code "71") (name "Net-(LED_SMD_15-PadVIN)") (class "Default")
      (node (ref "LED_SMD_15") (pin "VIN") (pinfunction "VIN_VIN") (pintype "input"))
      (node (ref "R35") (pin "1") (pinfunction "1_1") (pintype "passive"))
    )
    (net (code "72") (name "Net-(LED_SMD_16-PadVIN)") (class "Default")
      (node (ref "LED_SMD_16") (pin "VIN") (pinfunction "VIN_VIN") (pintype "input"))
      (node (ref "R37") (pin "1") (pinfunction "1_1") (pintype "passive"))
    )
    (net (code "73") (name "Net-(LED_SMD_17-PadVIN)") (class "Default")
      (node (ref "LED_SMD_17") (pin "VIN") (pinfunction "VIN_VIN") (pintype "input"))
      (node (ref "R39") (pin "1") (pinfunction "1_1") (pintype "passive"))
    )
    (net (code "74") (name "Net-(LED_SMD_18-PadVIN)") (class "Default")
      (node (ref "LED_SMD_18") (pin "VIN") (pinfunction "VIN_VIN") (pintype "input"))
      (node (ref "R41") (pin "1") (pinfunction "1_1") (pintype "passive"))
    )
    (net (code "75") (name "Net-(LED_SMD_19-PadVIN)") (class "Default")
      (node (ref "LED_SMD_19") (pin "VIN") (pinfunction "VIN_VIN") (pintype "input"))
      (node (ref "R43") (pin "1") (pinfunction "1_1") (pintype "passive"))
    )
    (net (code "76") (name "Net-(LED_SMD_20-PadVIN)") (class "Default")
      (node (ref "LED_SMD_20") (pin "VIN") (pinfunction "VIN_VIN") (pintype "input"))
      (node (ref "R45") (pin "1") (pinfunction "1_1") (pintype "passive"))
    )
    (net (code "77") (name "Net-(LED_SMD_21-PadVIN)") (class "Default")
      (node (ref "LED_SMD_21") (pin "VIN") (pinfunction "VIN_VIN") (pintype "input"))
      (node (ref "R47") (pin "1") (pinfunction "1_1") (pintype "passive"))
    )
    (net (code "78") (name "Net-(LED_SMD_22-PadVIN)") (class "Default")
      (node (ref "LED_SMD_22") (pin "VIN") (pinfunction "VIN_VIN") (pintype "input"))
      (node (ref "R49") (pin "1") (pinfunction "1_1") (pintype "passive"))
    )
    (net (code "79") (name "Net-(LED_SMD_23-PadVIN)") (class "Default")
      (node (ref "LED_SMD_23") (pin "VIN") (pinfunction "VIN_VIN") (pintype "input"))
      (node (ref "R51") (pin "1") (pinfunction "1_1") (pintype "passive"))
    )
    (net (code "80") (name "Net-(LED_SMD_24-PadVIN)") (class "Default")
      (node (ref "LED_SMD_24") (pin "VIN") (pinfunction "VIN_VIN") (pintype "input"))
      (node (ref "R53") (pin "1") (pinfunction "1_1") (pintype "passive"))
    )
    (net (code "81") (name "VCC_5V_0") (class "Default")
      (node (ref "C5") (pin "2") (pinfunction "2_2") (pintype "passive"))
      (node (ref "C6") (pin "2") (pinfunction "2_2") (pintype "passive"))
      (node (ref "D1") (pin "C") (pinfunction "C_C") (pintype "passive"))
      (node (ref "IC_1") (pin "18") (pinfunction "AVCC_18") (pintype "power_in"))
      (node (ref "IC_1") (pin "4") (pinfunction "VCC_4") (pintype "power_in"))
      (node (ref "JP3") (pin "2") (pinfunction "2_2") (pintype "passive"))
      (node (ref "PR_SMD_1") (pin "VIN") (pinfunction "VIN_VIN") (pintype "input"))
      (node (ref "PR_SMD_2") (pin "VIN") (pinfunction "VIN_VIN") (pintype "input"))
      (node (ref "PR_SMD_3") (pin "VIN") (pinfunction "VIN_VIN") (pintype "input"))
      (node (ref "PR_SMD_4") (pin "VIN") (pinfunction "VIN_VIN") (pintype "input"))
      (node (ref "PR_SMD_5") (pin "VIN") (pinfunction "VIN_VIN") (pintype "input"))
      (node (ref "PR_SMD_6") (pin "VIN") (pinfunction "VIN_VIN") (pintype "input"))
      (node (ref "PR_SMD_7") (pin "VIN") (pinfunction "VIN_VIN") (pintype "input"))
      (node (ref "PR_SMD_8") (pin "VIN") (pinfunction "VIN_VIN") (pintype "input"))
      (node (ref "R11") (pin "2") (pinfunction "2_2") (pintype "passive"))
      (node (ref "R13") (pin "2") (pinfunction "2_2") (pintype "passive"))
      (node (ref "R15") (pin "2") (pinfunction "2_2") (pintype "passive"))
      (node (ref "R17") (pin "2") (pinfunction "2_2") (pintype "passive"))
      (node (ref "R19") (pin "2") (pinfunction "2_2") (pintype "passive"))
      (node (ref "R21") (pin "2") (pinfunction "2_2") (pintype "passive"))
      (node (ref "R7") (pin "2") (pinfunction "2_2") (pintype "passive"))
      (node (ref "R9") (pin "2") (pinfunction "2_2") (pintype "passive"))
    )
    (net (code "82") (name "VCC_5V_1") (class "Default")
      (node (ref "C11") (pin "2") (pinfunction "2_2") (pintype "passive"))
      (node (ref "C12") (pin "2") (pinfunction "2_2") (pintype "passive"))
      (node (ref "D4") (pin "C") (pinfunction "C_C") (pintype "passive"))
      (node (ref "IC_2") (pin "18") (pinfunction "AVCC_18") (pintype "power_in"))
      (node (ref "IC_2") (pin "4") (pinfunction "VCC_4") (pintype "power_in"))
      (node (ref "JP4") (pin "2") (pinfunction "2_2") (pintype "passive"))
      (node (ref "PR_SMD_10") (pin "VIN") (pinfunction "VIN_VIN") (pintype "input"))
      (node (ref "PR_SMD_11") (pin "VIN") (pinfunction "VIN_VIN") (pintype "input"))
      (node (ref "PR_SMD_12") (pin "VIN") (pinfunction "VIN_VIN") (pintype "input"))
      (node (ref "PR_SMD_13") (pin "VIN") (pinfunction "VIN_VIN") (pintype "input"))
      (node (ref "PR_SMD_14") (pin "VIN") (pinfunction "VIN_VIN") (pintype "input"))
      (node (ref "PR_SMD_15") (pin "VIN") (pinfunction "VIN_VIN") (pintype "input"))
      (node (ref "PR_SMD_16") (pin "VIN") (pinfunction "VIN_VIN") (pintype "input"))
      (node (ref "PR_SMD_9") (pin "VIN") (pinfunction "VIN_VIN") (pintype "input"))
      (node (ref "R23") (pin "2") (pinfunction "2_2") (pintype "passive"))
      (node (ref "R25") (pin "2") (pinfunction "2_2") (pintype "passive"))
      (node (ref "R27") (pin "2") (pinfunction "2_2") (pintype "passive"))
      (node (ref "R29") (pin "2") (pinfunction "2_2") (pintype "passive"))
      (node (ref "R31") (pin "2") (pinfunction "2_2") (pintype "passive"))
      (node (ref "R33") (pin "2") (pinfunction "2_2") (pintype "passive"))
      (node (ref "R35") (pin "2") (pinfunction "2_2") (pintype "passive"))
      (node (ref "R37") (pin "2") (pinfunction "2_2") (pintype "passive"))
    )
    (net (code "83") (name "VCC_5V_2") (class "Default")
      (node (ref "C17") (pin "2") (pinfunction "2_2") (pintype "passive"))
      (node (ref "C18") (pin "2") (pinfunction "2_2") (pintype "passive"))
      (node (ref "D6") (pin "C") (pinfunction "C_C") (pintype "passive"))
      (node (ref "IC_3") (pin "18") (pinfunction "AVCC_18") (pintype "power_in"))
      (node (ref "IC_3") (pin "4") (pinfunction "VCC_4") (pintype "power_in"))
      (node (ref "JP5") (pin "2") (pinfunction "2_2") (pintype "passive"))
      (node (ref "PR_SMD_17") (pin "VIN") (pinfunction "VIN_VIN") (pintype "input"))
      (node (ref "PR_SMD_18") (pin "VIN") (pinfunction "VIN_VIN") (pintype "input"))
      (node (ref "PR_SMD_19") (pin "VIN") (pinfunction "VIN_VIN") (pintype "input"))
      (node (ref "PR_SMD_20") (pin "VIN") (pinfunction "VIN_VIN") (pintype "input"))
      (node (ref "PR_SMD_21") (pin "VIN") (pinfunction "VIN_VIN") (pintype "input"))
      (node (ref "PR_SMD_22") (pin "VIN") (pinfunction "VIN_VIN") (pintype "input"))
      (node (ref "PR_SMD_23") (pin "VIN") (pinfunction "VIN_VIN") (pintype "input"))
      (node (ref "PR_SMD_24") (pin "VIN") (pinfunction "VIN_VIN") (pintype "input"))
      (node (ref "R39") (pin "2") (pinfunction "2_2") (pintype "passive"))
      (node (ref "R41") (pin "2") (pinfunction "2_2") (pintype "passive"))
      (node (ref "R43") (pin "2") (pinfunction "2_2") (pintype "passive"))
      (node (ref "R45") (pin "2") (pinfunction "2_2") (pintype "passive"))
      (node (ref "R47") (pin "2") (pinfunction "2_2") (pintype "passive"))
      (node (ref "R49") (pin "2") (pinfunction "2_2") (pintype "passive"))
      (node (ref "R51") (pin "2") (pinfunction "2_2") (pintype "passive"))
      (node (ref "R53") (pin "2") (pinfunction "2_2") (pintype "passive"))
    )
    (net (code "84") (name "unconnected-(IC_1-PB0-Pad12)") (class "Default")
      (node (ref "IC_1") (pin "12") (pinfunction "PB0_12") (pintype "bidirectional"))
    )
    (net (code "85") (name "unconnected-(IC_1-PB1-Pad13)") (class "Default")
      (node (ref "IC_1") (pin "13") (pinfunction "PB1_13") (pintype "bidirectional"))
    )
    (net (code "86") (name "unconnected-(IC_1-PB2-Pad14)") (class "Default")
      (node (ref "IC_1") (pin "14") (pinfunction "PB2_14") (pintype "bidirectional"))
    )
    (net (code "87") (name "unconnected-(IC_1-PD0-Pad30)") (class "Default")
      (node (ref "IC_1") (pin "30") (pinfunction "PD0_30") (pintype "bidirectional"))
    )
    (net (code "88") (name "unconnected-(IC_1-PD1-Pad31)") (class "Default")
      (node (ref "IC_1") (pin "31") (pinfunction "PD1_31") (pintype "bidirectional"))
    )
    (net (code "89") (name "unconnected-(IC_1-PD2-Pad32)") (class "Default")
      (node (ref "IC_1") (pin "32") (pinfunction "PD2_32") (pintype "bidirectional"))
    )
    (net (code "90") (name "unconnected-(IC_1-PD3-Pad1)") (class "Default")
      (node (ref "IC_1") (pin "1") (pinfunction "PD3_1") (pintype "bidirectional"))
    )
    (net (code "91") (name "unconnected-(IC_1-PD4-Pad2)") (class "Default")
      (node (ref "IC_1") (pin "2") (pinfunction "PD4_2") (pintype "bidirectional"))
    )
    (net (code "92") (name "unconnected-(IC_1-PD5-Pad9)") (class "Default")
      (node (ref "IC_1") (pin "9") (pinfunction "PD5_9") (pintype "bidirectional"))
    )
    (net (code "93") (name "unconnected-(IC_1-PD6-Pad10)") (class "Default")
      (node (ref "IC_1") (pin "10") (pinfunction "PD6_10") (pintype "bidirectional"))
    )
    (net (code "94") (name "unconnected-(IC_1-PD7-Pad11)") (class "Default")
      (node (ref "IC_1") (pin "11") (pinfunction "PD7_11") (pintype "bidirectional"))
    )
    (net (code "95") (name "unconnected-(IC_2-PB0-Pad12)") (class "Default")
      (node (ref "IC_2") (pin "12") (pinfunction "PB0_12") (pintype "bidirectional"))
    )
    (net (code "96") (name "unconnected-(IC_2-PB1-Pad13)") (class "Default")
      (node (ref "IC_2") (pin "13") (pinfunction "PB1_13") (pintype "bidirectional"))
    )
    (net (code "97") (name "unconnected-(IC_2-PB2-Pad14)") (class "Default")
      (node (ref "IC_2") (pin "14") (pinfunction "PB2_14") (pintype "bidirectional"))
    )
    (net (code "98") (name "unconnected-(IC_2-PD0-Pad30)") (class "Default")
      (node (ref "IC_2") (pin "30") (pinfunction "PD0_30") (pintype "bidirectional"))
    )
    (net (code "99") (name "unconnected-(IC_2-PD1-Pad31)") (class "Default")
      (node (ref "IC_2") (pin "31") (pinfunction "PD1_31") (pintype "bidirectional"))
    )
    (net (code "100") (name "unconnected-(IC_2-PD2-Pad32)") (class "Default")
      (node (ref "IC_2") (pin "32") (pinfunction "PD2_32") (pintype "bidirectional"))
    )
    (net (code "101") (name "unconnected-(IC_2-PD3-Pad1)") (class "Default")
      (node (ref "IC_2") (pin "1") (pinfunction "PD3_1") (pintype "bidirectional"))
    )
    (net (code "102") (name "unconnected-(IC_2-PD4-Pad2)") (class "Default")
      (node (ref "IC_2") (pin "2") (pinfunction "PD4_2") (pintype "bidirectional"))
    )
    (net (code "103") (name "unconnected-(IC_2-PD5-Pad9)") (class "Default")
      (node (ref "IC_2") (pin "9") (pinfunction "PD5_9") (pintype "bidirectional"))
    )
    (net (code "104") (name "unconnected-(IC_2-PD6-Pad10)") (class "Default")
      (node (ref "IC_2") (pin "10") (pinfunction "PD6_10") (pintype "bidirectional"))
    )
    (net (code "105") (name "unconnected-(IC_2-PD7-Pad11)") (class "Default")
      (node (ref "IC_2") (pin "11") (pinfunction "PD7_11") (pintype "bidirectional"))
    )
    (net (code "106") (name "unconnected-(IC_3-PB0-Pad12)") (class "Default")
      (node (ref "IC_3") (pin "12") (pinfunction "PB0_12") (pintype "bidirectional"))
    )
    (net (code "107") (name "unconnected-(IC_3-PB1-Pad13)") (class "Default")
      (node (ref "IC_3") (pin "13") (pinfunction "PB1_13") (pintype "bidirectional"))
    )
    (net (code "108") (name "unconnected-(IC_3-PB2-Pad14)") (class "Default")
      (node (ref "IC_3") (pin "14") (pinfunction "PB2_14") (pintype "bidirectional"))
    )
    (net (code "109") (name "unconnected-(IC_3-PD0-Pad30)") (class "Default")
      (node (ref "IC_3") (pin "30") (pinfunction "PD0_30") (pintype "bidirectional"))
    )
    (net (code "110") (name "unconnected-(IC_3-PD1-Pad31)") (class "Default")
      (node (ref "IC_3") (pin "31") (pinfunction "PD1_31") (pintype "bidirectional"))
    )
    (net (code "111") (name "unconnected-(IC_3-PD2-Pad32)") (class "Default")
      (node (ref "IC_3") (pin "32") (pinfunction "PD2_32") (pintype "bidirectional"))
    )
    (net (code "112") (name "unconnected-(IC_3-PD3-Pad1)") (class "Default")
      (node (ref "IC_3") (pin "1") (pinfunction "PD3_1") (pintype "bidirectional"))
    )
    (net (code "113") (name "unconnected-(IC_3-PD4-Pad2)") (class "Default")
      (node (ref "IC_3") (pin "2") (pinfunction "PD4_2") (pintype "bidirectional"))
    )
    (net (code "114") (name "unconnected-(IC_3-PD5-Pad9)") (class "Default")
      (node (ref "IC_3") (pin "9") (pinfunction "PD5_9") (pintype "bidirectional"))
    )
    (net (code "115") (name "unconnected-(IC_3-PD6-Pad10)") (class "Default")
      (node (ref "IC_3") (pin "10") (pinfunction "PD6_10") (pintype "bidirectional"))
    )
    (net (code "116") (name "unconnected-(IC_3-PD7-Pad11)") (class "Default")
      (node (ref "IC_3") (pin "11") (pinfunction "PD7_11") (pintype "bidirectional"))
    )
  )
)
